# Power.net
KiCad netlist of a schematic drawn in Altium Designer
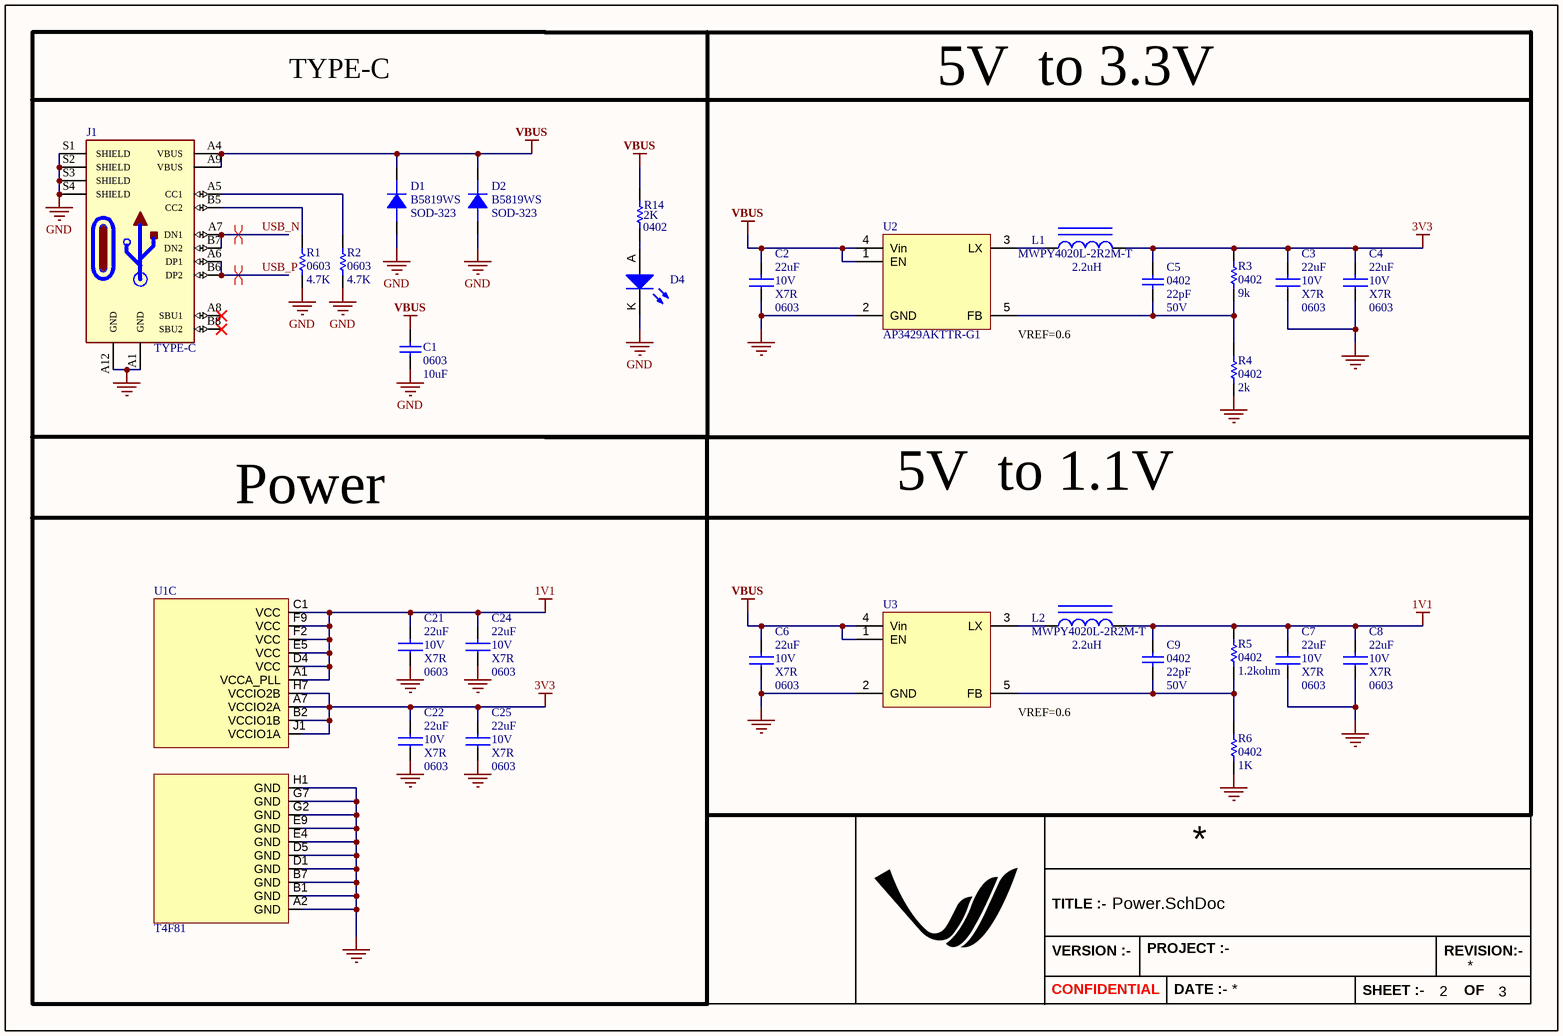
[diagram p0: Power.SchDoc]

(export (version "E")
  (design (tool "Eeschema 10.0.6"))
  (components
    (comp (ref "C1")
      (value "10uF")
      (footprint "CAPC0603")
      (description "Ceramic Capacitor, 10uF, 0603,10V")
      (fields (field (name "CASE/PACKAGE") "0603") (field (name "Comment") "Capacitor"))
      (libsource (lib "") (part "Capacitor_1"))
    )
    (comp (ref "C2")
      (value "22uF")
      (footprint "CAPC0603")
      (description "CAP CER 22uF 10V X7R 0603")
      (fields
        (field (name "MANUFACTURER PART NUMBER") "CC0603KRX7R6BB226")
        (field (name "VOLTAGE") "10V")
        (field (name "DIELECTRIC") "X7R")
        (field (name "CASE/PACKAGE") "0603")
      )
      (libsource (lib "CUSTOM SCH") (part "Cap"))
    )
    (comp (ref "C3")
      (value "22uF")
      (footprint "CAPC0603")
      (description "CAP CER 22uF 10V X7R 0603")
      (fields
        (field (name "MANUFACTURER PART NUMBER") "CC0603KRX7R6BB226")
        (field (name "VOLTAGE") "10V")
        (field (name "DIELECTRIC") "X7R")
        (field (name "CASE/PACKAGE") "0603")
      )
      (libsource (lib "CUSTOM SCH") (part "Cap"))
    )
    (comp (ref "C4")
      (value "22uF")
      (footprint "CAPC0603")
      (description "CAP CER 22uF 10V X7R 0603")
      (fields
        (field (name "MANUFACTURER PART NUMBER") "CC0603KRX7R6BB226")
        (field (name "VOLTAGE") "10V")
        (field (name "DIELECTRIC") "X7R")
        (field (name "CASE/PACKAGE") "0603")
      )
      (libsource (lib "CUSTOM SCH") (part "Cap"))
    )
    (comp (ref "C5")
      (value "22pF")
      (footprint "CAPC0402")
      (description "Ceramic Capacitor, 22pF, 0402,50V")
      (fields (field (name "CASE/PACKAGE") "0402") (field (name "VOLTAGE") "50V"))
      (libsource (lib "Pd's Sch Lib") (part "Capacitor"))
    )
    (comp (ref "C6")
      (value "22uF")
      (footprint "CAPC0603")
      (description "CAP CER 22uF 10V X7R 0603")
      (fields
        (field (name "MANUFACTURER PART NUMBER") "CC0603KRX7R6BB226")
        (field (name "VOLTAGE") "10V")
        (field (name "DIELECTRIC") "X7R")
        (field (name "CASE/PACKAGE") "0603")
      )
      (libsource (lib "CUSTOM SCH") (part "Cap"))
    )
    (comp (ref "C7")
      (value "22uF")
      (footprint "CAPC0603")
      (description "CAP CER 22uF 10V X7R 0603")
      (fields
        (field (name "MANUFACTURER PART NUMBER") "CC0603KRX7R6BB226")
        (field (name "VOLTAGE") "10V")
        (field (name "DIELECTRIC") "X7R")
        (field (name "CASE/PACKAGE") "0603")
      )
      (libsource (lib "CUSTOM SCH") (part "Cap"))
    )
    (comp (ref "C8")
      (value "22uF")
      (footprint "CAPC0603")
      (description "CAP CER 22uF 10V X7R 0603")
      (fields
        (field (name "MANUFACTURER PART NUMBER") "CC0603KRX7R6BB226")
        (field (name "VOLTAGE") "10V")
        (field (name "DIELECTRIC") "X7R")
        (field (name "CASE/PACKAGE") "0603")
      )
      (libsource (lib "CUSTOM SCH") (part "Cap"))
    )
    (comp (ref "C9")
      (value "22pF")
      (footprint "CAPC0402")
      (description "Ceramic Capacitor, 22pF, 0402,50V")
      (fields (field (name "CASE/PACKAGE") "0402") (field (name "VOLTAGE") "50V"))
      (libsource (lib "Pd's Sch Lib") (part "Capacitor"))
    )
    (comp (ref "C21")
      (value "22uF")
      (footprint "CAPC0603")
      (description "CAP CER 22uF 10V X7R 0603")
      (fields
        (field (name "MANUFACTURER PART NUMBER") "CC0603KRX7R6BB226")
        (field (name "VOLTAGE") "10V")
        (field (name "DIELECTRIC") "X7R")
        (field (name "CASE/PACKAGE") "0603")
      )
      (libsource (lib "CUSTOM SCH") (part "Cap"))
    )
    (comp (ref "C22")
      (value "22uF")
      (footprint "CAPC0603")
      (description "CAP CER 22uF 10V X7R 0603")
      (fields
        (field (name "MANUFACTURER PART NUMBER") "CC0603KRX7R6BB226")
        (field (name "VOLTAGE") "10V")
        (field (name "DIELECTRIC") "X7R")
        (field (name "CASE/PACKAGE") "0603")
      )
      (libsource (lib "CUSTOM SCH") (part "Cap"))
    )
    (comp (ref "C24")
      (value "22uF")
      (footprint "CAPC0603")
      (description "CAP CER 22uF 10V X7R 0603")
      (fields
        (field (name "MANUFACTURER PART NUMBER") "CC0603KRX7R6BB226")
        (field (name "VOLTAGE") "10V")
        (field (name "DIELECTRIC") "X7R")
        (field (name "CASE/PACKAGE") "0603")
      )
      (libsource (lib "CUSTOM SCH") (part "Cap"))
    )
    (comp (ref "C25")
      (value "22uF")
      (footprint "CAPC0603")
      (description "CAP CER 22uF 10V X7R 0603")
      (fields
        (field (name "MANUFACTURER PART NUMBER") "CC0603KRX7R6BB226")
        (field (name "VOLTAGE") "10V")
        (field (name "DIELECTRIC") "X7R")
        (field (name "CASE/PACKAGE") "0603")
      )
      (libsource (lib "CUSTOM SCH") (part "Cap"))
    )
    (comp (ref "D1")
      (value "DIODE_B5819WS")
      (footprint "SOD-323")
      (description "Schottky Barrier，B5819WS SOD-323")
      (fields (field (name "MANUFACTURER PART NUMBER") "B5819WS") (field (name "CASE/PACKAGE") "SOD-323"))
      (libsource (lib "CUSTOM SCH") (part "DIODE_B5819WS"))
    )
    (comp (ref "D2")
      (value "DIODE_B5819WS")
      (footprint "SOD-323")
      (description "Schottky Barrier，B5819WS SOD-323")
      (fields (field (name "MANUFACTURER PART NUMBER") "B5819WS") (field (name "CASE/PACKAGE") "SOD-323"))
      (libsource (lib "CUSTOM SCH") (part "DIODE_B5819WS"))
    )
    (comp (ref "D4")
      (value "~")
      (footprint "led_0603")
      (description "RED LED 0603")
      (fields (field (name "MANUFACTURER PART NUMBER") "GREEN"))
      (libsource (lib "CUSTOM TNY290PG") (part "LED1"))
    )
    (comp (ref "J1")
      (value "TYPE-C")
      (footprint "TYPE-C")
      (fields (field (name "MANUFACTURER PART NUMBER") "C167321"))
      (libsource (lib "Pd's Sch Lib") (part "TYPE-C"))
    )
    (comp (ref "L1")
      (value "2.2uH")
      (footprint "IND_4.0X4.0X2.0")
      (description "2.2uH, 48mOhm, 4.35A, 6.12A, ±20%, SMD,4x4x2mm, Power Inductor (MWPY4020L-2R2M-T) (C2934996)")
      (fields (field (name "MANUFACTURER PART NUMBER") "MWPY4020L-2R2M-T") (field (name "Comment") "IND_1"))
      (libsource (lib "CUSTOM SCH") (part "IND_1"))
    )
    (comp (ref "L2")
      (value "2.2uH")
      (footprint "IND_4.0X4.0X2.0")
      (description "2.2uH, 48mOhm, 4.35A, 6.12A, ±20%, SMD,4x4x2mm, Power Inductor (MWPY4020L-2R2M-T) (C2934996)")
      (fields (field (name "MANUFACTURER PART NUMBER") "MWPY4020L-2R2M-T") (field (name "Comment") "IND_1"))
      (libsource (lib "CUSTOM SCH") (part "IND_1"))
    )
    (comp (ref "R1")
      (value "4.7K")
      (footprint "RESC0603")
      (description "Thick Film Resistor -  4.7Kohm, 1%, 0603")
      (fields (field (name "CASE/PACKAGE") "0603") (field (name "Comment") "Resistor"))
      (libsource (lib "Pd's Sch Lib") (part "Resistor"))
    )
    (comp (ref "R2")
      (value "4.7K")
      (footprint "RESC0603")
      (description "Thick Film Resistor -  4.7Kohm, 1%, 0603")
      (fields (field (name "CASE/PACKAGE") "0603") (field (name "Comment") "Resistor"))
      (libsource (lib "Pd's Sch Lib") (part "Resistor"))
    )
    (comp (ref "R3")
      (value "9k")
      (footprint "resc0402")
      (description "Thick Film Resistor -  9Kohm, 1%, 0402")
      (fields
        (field (name "CASE/PACKAGE") "0402")
        (field (name "TOLERANCE") "1%")
        (field (name "Comment") "Res1")
      )
      (libsource (lib "Miscellaneous Devices") (part "Res1"))
    )
    (comp (ref "R4")
      (value "2k")
      (footprint "resc0402")
      (description "Thick Film Resistor -  2Kohm, 1%, 0402")
      (fields
        (field (name "CASE/PACKAGE") "0402")
        (field (name "TOLERANCE") "1%")
        (field (name "Comment") "Res1")
      )
      (libsource (lib "Miscellaneous Devices") (part "Res1"))
    )
    (comp (ref "R5")
      (value "1.2kohm")
      (footprint "resc0402")
      (description "Thick Film Resistor -  1.2kohm, 1%, 0402")
      (fields
        (field (name "CASE/PACKAGE") "0402")
        (field (name "TOLERANCE") "1%")
        (field (name "Comment") "Res1")
      )
      (libsource (lib "Miscellaneous Devices") (part "Res1"))
    )
    (comp (ref "R6")
      (value "1K")
      (footprint "resc0402")
      (description "Thick Film Resistor -  1Kohm, 1%, 0402")
      (fields
        (field (name "MANUFACTURER PART NUMBER") "0402WGF1001TCE")
        (field (name "CASE/PACKAGE") "0402")
        (field (name "TOLERANCE") "1%")
      )
      (libsource (lib "Miscellaneous Devices") (part "Res1"))
    )
    (comp (ref "R14")
      (value "2K")
      (footprint "resc0402")
      (description "Thick Film Resistor -  2Kohm, 1%, 0402")
      (fields (field (name "CASE/PACKAGE") "0402") (field (name "Comment") "Res1"))
      (libsource (lib "Miscellaneous Devices") (part "Res1"))
    )
    (comp (ref "U1") (value "T4F81") (footprint "T4F81 fpga") (libsource (lib "CUSTOM SCH") (part "T4F81")))
    (comp (ref "U2")
      (value "AP3429")
      (footprint "SOT23-5")
      (description "Buck Switching Regulator IC Positive Adjustable 0.6V 1 Output 2A SOT-23-5 Thin, TSOT-23-5")
      (fields (field (name "MANUFACTURER PART NUMBER") "AP3429AKTTR-G1"))
      (libsource (lib "CUSTOM SCH") (part "AP3429"))
    )
    (comp (ref "U3")
      (value "AP3429")
      (footprint "SOT23-5")
      (description "Buck Switching Regulator IC Positive Adjustable 0.6V 1 Output 2A SOT-23-5 Thin, TSOT-23-5")
      (libsource (lib "CUSTOM SCH") (part "AP3429"))
    )
  )
  (nets
    (net (code "1") (name "/USB_N") (class "Default")
      (node (ref "J1") (pin "A7") (pinfunction "DN1_A7") (pintype "bidirectional"))
      (node (ref "J1") (pin "B7") (pinfunction "DN2_B7") (pintype "bidirectional"))
    )
    (net (code "2") (name "/USB_P") (class "Default")
      (node (ref "J1") (pin "A6") (pinfunction "DP1_A6") (pintype "bidirectional"))
      (node (ref "J1") (pin "B6") (pinfunction "DP2_B6") (pintype "bidirectional"))
    )
    (net (code "3") (name "1V1") (class "Default")
      (node (ref "C21") (pin "2") (pinfunction "2_2") (pintype "passive"))
      (node (ref "C24") (pin "2") (pinfunction "2_2") (pintype "passive"))
      (node (ref "C7") (pin "2") (pinfunction "2_2") (pintype "passive"))
      (node (ref "C8") (pin "2") (pinfunction "2_2") (pintype "passive"))
      (node (ref "C9") (pin "2") (pinfunction "2_2") (pintype "passive"))
      (node (ref "L2") (pin "2") (pinfunction "2_2") (pintype "passive"))
      (node (ref "R5") (pin "1") (pinfunction "1_1") (pintype "passive"))
      (node (ref "U1") (pin "A1") (pinfunction "VCCA_PLL_A1") (pintype "passive"))
      (node (ref "U1") (pin "C1") (pinfunction "VCC_C1") (pintype "passive"))
      (node (ref "U1") (pin "D4") (pinfunction "VCC_D4") (pintype "passive"))
      (node (ref "U1") (pin "E5") (pinfunction "VCC_E5") (pintype "passive"))
      (node (ref "U1") (pin "F2") (pinfunction "VCC_F2") (pintype "passive"))
      (node (ref "U1") (pin "F9") (pinfunction "VCC_F9") (pintype "passive"))
    )
    (net (code "4") (name "3V3") (class "Default")
      (node (ref "C22") (pin "2") (pinfunction "2_2") (pintype "passive"))
      (node (ref "C25") (pin "2") (pinfunction "2_2") (pintype "passive"))
      (node (ref "C3") (pin "2") (pinfunction "2_2") (pintype "passive"))
      (node (ref "C4") (pin "2") (pinfunction "2_2") (pintype "passive"))
      (node (ref "C5") (pin "2") (pinfunction "2_2") (pintype "passive"))
      (node (ref "L1") (pin "2") (pinfunction "2_2") (pintype "passive"))
      (node (ref "R3") (pin "1") (pinfunction "1_1") (pintype "passive"))
      (node (ref "U1") (pin "A7") (pinfunction "VCCIO2A_A7") (pintype "passive"))
      (node (ref "U1") (pin "B2") (pinfunction "VCCIO1B_B2") (pintype "passive"))
      (node (ref "U1") (pin "H7") (pinfunction "VCCIO2B_H7") (pintype "passive"))
      (node (ref "U1") (pin "J1") (pinfunction "VCCIO1A_J1") (pintype "passive"))
    )
    (net (code "5") (name "GND") (class "Default")
      (node (ref "C1") (pin "2") (pinfunction "2_2") (pintype "passive"))
      (node (ref "C2") (pin "1") (pinfunction "1_1") (pintype "passive"))
      (node (ref "C21") (pin "1") (pinfunction "1_1") (pintype "passive"))
      (node (ref "C22") (pin "1") (pinfunction "1_1") (pintype "passive"))
      (node (ref "C24") (pin "1") (pinfunction "1_1") (pintype "passive"))
      (node (ref "C25") (pin "1") (pinfunction "1_1") (pintype "passive"))
      (node (ref "C3") (pin "1") (pinfunction "1_1") (pintype "passive"))
      (node (ref "C4") (pin "1") (pinfunction "1_1") (pintype "passive"))
      (node (ref "C6") (pin "1") (pinfunction "1_1") (pintype "passive"))
      (node (ref "C7") (pin "1") (pinfunction "1_1") (pintype "passive"))
      (node (ref "C8") (pin "1") (pinfunction "1_1") (pintype "passive"))
      (node (ref "D1") (pin "1") (pinfunction "A_1") (pintype "passive"))
      (node (ref "D2") (pin "1") (pinfunction "A_1") (pintype "passive"))
      (node (ref "D4") (pin "K") (pinfunction "K_K") (pintype "passive"))
      (node (ref "J1") (pin "A1") (pinfunction "GND_A1") (pintype "power_in"))
      (node (ref "J1") (pin "A12") (pinfunction "GND_A12") (pintype "power_in"))
      (node (ref "J1") (pin "S1") (pinfunction "SHIELD_S1") (pintype "passive"))
      (node (ref "J1") (pin "S2") (pinfunction "SHIELD_S2") (pintype "passive"))
      (node (ref "J1") (pin "S3") (pinfunction "SHIELD_S3") (pintype "passive"))
      (node (ref "J1") (pin "S4") (pinfunction "SHIELD_S4") (pintype "passive"))
      (node (ref "R1") (pin "1") (pinfunction "1_1") (pintype "passive"))
      (node (ref "R2") (pin "1") (pinfunction "1_1") (pintype "passive"))
      (node (ref "R4") (pin "2") (pinfunction "2_2") (pintype "passive"))
      (node (ref "R6") (pin "2") (pinfunction "2_2") (pintype "passive"))
      (node (ref "U1") (pin "A2") (pinfunction "GND_A2") (pintype "passive"))
      (node (ref "U1") (pin "B1") (pinfunction "GND_B1") (pintype "passive"))
      (node (ref "U1") (pin "B7") (pinfunction "GND_B7") (pintype "passive"))
      (node (ref "U1") (pin "D1") (pinfunction "GND_D1") (pintype "passive"))
      (node (ref "U1") (pin "D5") (pinfunction "GND_D5") (pintype "passive"))
      (node (ref "U1") (pin "E4") (pinfunction "GND_E4") (pintype "passive"))
      (node (ref "U1") (pin "E9") (pinfunction "GND_E9") (pintype "passive"))
      (node (ref "U1") (pin "G2") (pinfunction "GND_G2") (pintype "passive"))
      (node (ref "U1") (pin "G7") (pinfunction "GND_G7") (pintype "passive"))
      (node (ref "U1") (pin "H1") (pinfunction "GND_H1") (pintype "passive"))
      (node (ref "U2") (pin "2") (pinfunction "GND_2") (pintype "passive"))
      (node (ref "U3") (pin "2") (pinfunction "GND_2") (pintype "passive"))
    )
    (net (code "6") (name "Net-(D4-PadA)") (class "Default")
      (node (ref "D4") (pin "A") (pinfunction "A_A") (pintype "passive"))
      (node (ref "R14") (pin "2") (pinfunction "2_2") (pintype "passive"))
    )
    (net (code "7") (name "Net-(J1-CC1)") (class "Default")
      (node (ref "J1") (pin "A5") (pinfunction "CC1_A5") (pintype "bidirectional"))
      (node (ref "R2") (pin "2") (pinfunction "2_2") (pintype "passive"))
    )
    (net (code "8") (name "Net-(J1-CC2)") (class "Default")
      (node (ref "J1") (pin "B5") (pinfunction "CC2_B5") (pintype "bidirectional"))
      (node (ref "R1") (pin "2") (pinfunction "2_2") (pintype "passive"))
    )
    (net (code "9") (name "Net-(U2-FB)") (class "Default")
      (node (ref "C5") (pin "1") (pinfunction "1_1") (pintype "passive"))
      (node (ref "R3") (pin "2") (pinfunction "2_2") (pintype "passive"))
      (node (ref "R4") (pin "1") (pinfunction "1_1") (pintype "passive"))
      (node (ref "U2") (pin "5") (pinfunction "FB_5") (pintype "power_in"))
    )
    (net (code "10") (name "Net-(U2-LX)") (class "Default")
      (node (ref "L1") (pin "1") (pinfunction "1_1") (pintype "passive"))
      (node (ref "U2") (pin "3") (pinfunction "LX_3") (pintype "passive"))
    )
    (net (code "11") (name "Net-(U3-FB)") (class "Default")
      (node (ref "C9") (pin "1") (pinfunction "1_1") (pintype "passive"))
      (node (ref "R5") (pin "2") (pinfunction "2_2") (pintype "passive"))
      (node (ref "R6") (pin "1") (pinfunction "1_1") (pintype "passive"))
      (node (ref "U3") (pin "5") (pinfunction "FB_5") (pintype "power_in"))
    )
    (net (code "12") (name "Net-(U3-LX)") (class "Default")
      (node (ref "L2") (pin "1") (pinfunction "1_1") (pintype "passive"))
      (node (ref "U3") (pin "3") (pinfunction "LX_3") (pintype "passive"))
    )
    (net (code "13") (name "VBUS") (class "Default")
      (node (ref "C1") (pin "1") (pinfunction "1_1") (pintype "passive"))
      (node (ref "C2") (pin "2") (pinfunction "2_2") (pintype "passive"))
      (node (ref "C6") (pin "2") (pinfunction "2_2") (pintype "passive"))
      (node (ref "D1") (pin "2") (pinfunction "K_2") (pintype "passive"))
      (node (ref "D2") (pin "2") (pinfunction "K_2") (pintype "passive"))
      (node (ref "J1") (pin "A4") (pinfunction "VBUS_A4") (pintype "power_in"))
      (node (ref "J1") (pin "A9") (pinfunction "VBUS_A9") (pintype "power_in"))
      (node (ref "R14") (pin "1") (pinfunction "1_1") (pintype "passive"))
      (node (ref "U2") (pin "1") (pinfunction "EN_1") (pintype "power_in"))
      (node (ref "U2") (pin "4") (pinfunction "Vin_4") (pintype "power_in"))
      (node (ref "U3") (pin "1") (pinfunction "EN_1") (pintype "power_in"))
      (node (ref "U3") (pin "4") (pinfunction "Vin_4") (pintype "power_in"))
    )
    (net (code "14") (name "unconnected-(J1-SBU1-PadA8)") (class "Default")
      (node (ref "J1") (pin "A8") (pinfunction "SBU1_A8") (pintype "bidirectional+no_connect"))
    )
    (net (code "15") (name "unconnected-(J1-SBU2-PadB8)") (class "Default")
      (node (ref "J1") (pin "B8") (pinfunction "SBU2_B8") (pintype "bidirectional+no_connect"))
    )
  )
)
